# Voltage_Regulator.net
KiCad netlist of a schematic drawn in Altium Designer
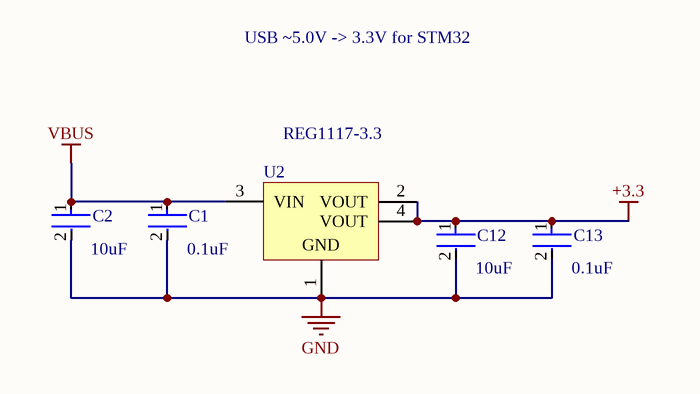
[diagram p0: Voltage_Regulator.SchDoc]

(export (version "E")
  (design (tool "Eeschema 10.0.6"))
  (components
    (comp (ref "C1")
      (value "0.1uF")
      (footprint "CAPC0603(1608)100_L")
      (description "GENERIC CAPACITOR 0805 or 0603(1608)")
      (libsource (lib "Sooner Competitive Robotics") (part "11868f565c42a9108669ba33697ecf6"))
    )
    (comp (ref "C2")
      (value "10uF")
      (footprint "CAPC0603(1608)100_L")
      (description "GENERIC CAPACITOR 0805 or 0603(1608)")
      (libsource (lib "Sooner Competitive Robotics") (part "11868f565c42a9108669ba33697ecf6"))
    )
    (comp (ref "C12")
      (value "10uF")
      (footprint "CAPC0603(1608)100_L")
      (description "GENERIC CAPACITOR 0805 or 0603(1608)")
      (libsource (lib "Sooner Competitive Robotics") (part "11868f565c42a9108669ba33697ecf6"))
    )
    (comp (ref "C13")
      (value "0.1uF")
      (footprint "CAPC0603(1608)100_L")
      (description "GENERIC CAPACITOR 0805 or 0603(1608)")
      (libsource (lib "Sooner Competitive Robotics") (part "11868f565c42a9108669ba33697ecf6"))
    )
    (comp (ref "U2")
      (value "REG1117-3.3")
      (footprint "DCY0004A_M")
      (description "LDO Regulator Pos 3.3V 0.8A 4-Pin(3+Tab) SOT-223 Rail")
      (libsource (lib "Sooner Competitive Robotics") (part "TI-REG1117-XXXX"))
    )
  )
  (nets
    (net (code "1") (name "+3.3") (class "Default")
      (node (ref "C12") (pin "1") (pinfunction "1_1") (pintype "passive"))
      (node (ref "C13") (pin "1") (pinfunction "1_1") (pintype "passive"))
      (node (ref "U2") (pin "2") (pinfunction "VOUT_2") (pintype "power_in"))
      (node (ref "U2") (pin "4") (pinfunction "VOUT_4") (pintype "power_in"))
    )
    (net (code "2") (name "GND") (class "Default")
      (node (ref "C1") (pin "2") (pinfunction "2_2") (pintype "passive"))
      (node (ref "C12") (pin "2") (pinfunction "2_2") (pintype "passive"))
      (node (ref "C13") (pin "2") (pinfunction "2_2") (pintype "passive"))
      (node (ref "C2") (pin "2") (pinfunction "2_2") (pintype "passive"))
      (node (ref "U2") (pin "1") (pinfunction "GND_1") (pintype "power_in"))
    )
    (net (code "3") (name "VBUS") (class "Default")
      (node (ref "C1") (pin "1") (pinfunction "1_1") (pintype "passive"))
      (node (ref "C2") (pin "1") (pinfunction "1_1") (pintype "passive"))
      (node (ref "U2") (pin "3") (pinfunction "VIN_3") (pintype "power_in"))
    )
  )
)
